# SMH118.net
KiCad netlist of a schematic drawn in Altium Designer
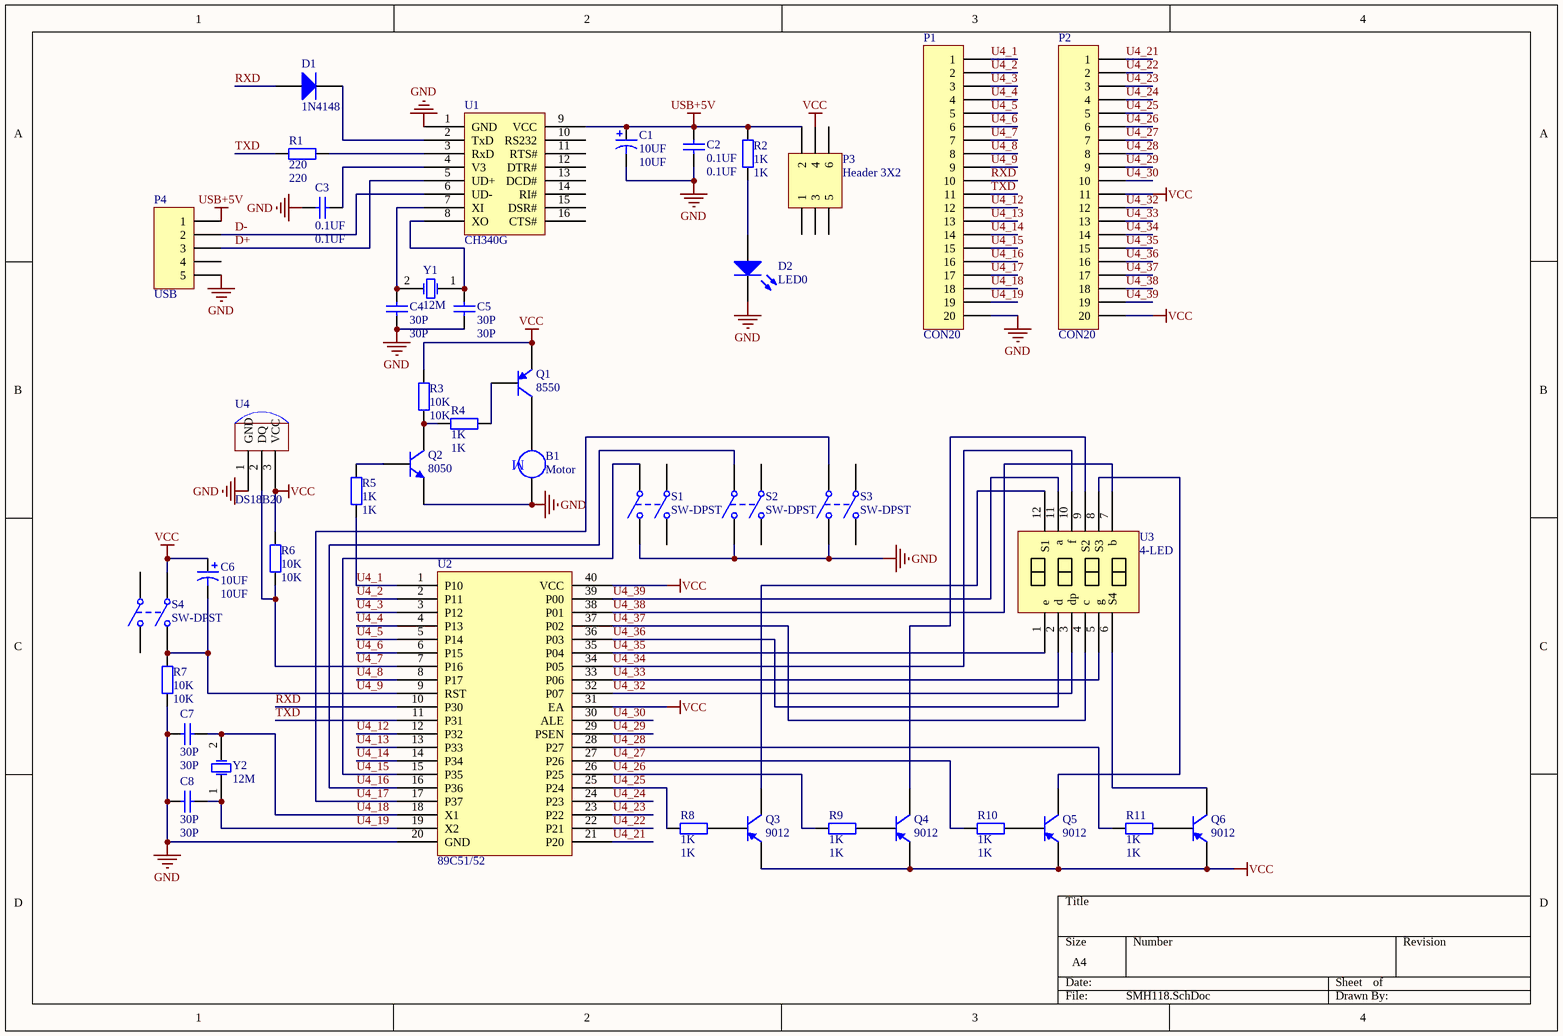
[diagram p0: SMH118.SchDoc]

(export (version "E")
  (design (tool "Eeschema 10.0.6"))
  (components
    (comp (ref "B1")
      (value "Motor")
      (footprint "XH2.54-2P")
      (description "Motor, General Kind")
      (fields (field (name "PUBLISHER") "Altium Limited"))
      (libsource (lib "Miscellaneous Devices") (part "Motor"))
    )
    (comp (ref "C1")
      (value "10UF")
      (footprint "CD4")
      (description "Polarized Capacitor (Radial)")
      (fields (field (name "ALTIUM_VALUE") "10UF") (field (name "PUBLISHER") "Altium Limited"))
      (libsource (lib "") (part "Cap Pol1_1"))
    )
    (comp (ref "C2")
      (value "0.1UF")
      (footprint "CB1")
      (description "Capacitor")
      (fields (field (name "ALTIUM_VALUE") "0.1UF") (field (name "PUBLISHER") "Altium Limited"))
      (libsource (lib "Miscellaneous Devices") (part "Cap"))
    )
    (comp (ref "C3")
      (value "0.1UF")
      (footprint "CB1")
      (description "Capacitor")
      (fields (field (name "ALTIUM_VALUE") "0.1UF") (field (name "PUBLISHER") "Altium Limited"))
      (libsource (lib "Miscellaneous Devices") (part "Cap"))
    )
    (comp (ref "C4")
      (value "30P")
      (footprint "CB1")
      (description "Capacitor")
      (fields (field (name "ALTIUM_VALUE") "30P") (field (name "PUBLISHER") "Altium Limited"))
      (libsource (lib "Miscellaneous Devices") (part "Cap"))
    )
    (comp (ref "C5")
      (value "30P")
      (footprint "CB1")
      (description "Capacitor")
      (fields (field (name "ALTIUM_VALUE") "30P") (field (name "PUBLISHER") "Altium Limited"))
      (libsource (lib "Miscellaneous Devices") (part "Cap"))
    )
    (comp (ref "C6")
      (value "10UF")
      (footprint "CD4")
      (description "Polarized Capacitor (Radial)")
      (fields (field (name "ALTIUM_VALUE") "10UF") (field (name "PUBLISHER") "Altium Limited"))
      (libsource (lib "Miscellaneous Devices") (part "Cap Pol1"))
    )
    (comp (ref "C7")
      (value "30P")
      (footprint "CB1")
      (description "Capacitor")
      (fields (field (name "ALTIUM_VALUE") "30P") (field (name "PUBLISHER") "Altium Limited"))
      (libsource (lib "Miscellaneous Devices") (part "Cap"))
    )
    (comp (ref "C8")
      (value "30P")
      (footprint "CB1")
      (description "Capacitor")
      (fields (field (name "ALTIUM_VALUE") "30P") (field (name "PUBLISHER") "Altium Limited"))
      (libsource (lib "Miscellaneous Devices") (part "Cap"))
    )
    (comp (ref "D1")
      (value "1N4148")
      (footprint "DIODE0.3")
      (description "High Conductance Fast Diode")
      (fields (field (name "PUBLISHER") "Altium Limited"))
      (libsource (lib "SMH118") (part "Diode 1N4148"))
    )
    (comp (ref "D2")
      (value "LED0")
      (footprint "LED3")
      (description "Typical INFRARED GaAs LED")
      (fields (field (name "PUBLISHER") "Altium Limited"))
      (libsource (lib "Miscellaneous Devices") (part "LED0"))
    )
    (comp (ref "P1")
      (value "CON20")
      (footprint "SIP20")
      (description "Header, 20-Pin")
      (fields (field (name "PUBLISHER") "Altium Limited"))
      (libsource (lib "Miscellaneous Connectors") (part "Header 20"))
    )
    (comp (ref "P2")
      (value "CON20")
      (footprint "SIP20")
      (description "Header, 20-Pin")
      (fields (field (name "PUBLISHER") "Altium Limited"))
      (libsource (lib "Miscellaneous Connectors") (part "Header 20"))
    )
    (comp (ref "P3")
      (value "Header 3X2")
      (footprint "SW6 - 2")
      (description "Header, 3-Pin, Dual row")
      (fields (field (name "PUBLISHER") "Altium Limited"))
      (libsource (lib "Miscellaneous Connectors") (part "Header 3X2"))
    )
    (comp (ref "P4")
      (value "USB")
      (footprint "MINIUSB")
      (description "Header, 5-Pin")
      (fields (field (name "PUBLISHER") "Altium Limited"))
      (libsource (lib "Miscellaneous Connectors") (part "Header 5"))
    )
    (comp (ref "Q1")
      (value "8550")
      (footprint "8050")
      (description "PNP Bipolar Transistor")
      (fields (field (name "PUBLISHER") "Altium Limited"))
      (libsource (lib "Miscellaneous Devices") (part "PNP"))
    )
    (comp (ref "Q2")
      (value "8050")
      (footprint "8050")
      (description "NPN Bipolar Transistor")
      (fields (field (name "PUBLISHER") "Altium Limited"))
      (libsource (lib "Miscellaneous Devices") (part "NPN"))
    )
    (comp (ref "Q3")
      (value "9012")
      (footprint "8050")
      (description "PNP Bipolar Transistor")
      (fields (field (name "PUBLISHER") "Altium Limited"))
      (libsource (lib "Miscellaneous Devices") (part "PNP"))
    )
    (comp (ref "Q4")
      (value "9012")
      (footprint "8050")
      (description "PNP Bipolar Transistor")
      (fields (field (name "PUBLISHER") "Altium Limited"))
      (libsource (lib "Miscellaneous Devices") (part "PNP"))
    )
    (comp (ref "Q5")
      (value "9012")
      (footprint "8050")
      (description "PNP Bipolar Transistor")
      (fields (field (name "PUBLISHER") "Altium Limited"))
      (libsource (lib "Miscellaneous Devices") (part "PNP"))
    )
    (comp (ref "Q6")
      (value "9012")
      (footprint "8050")
      (description "PNP Bipolar Transistor")
      (fields (field (name "PUBLISHER") "Altium Limited"))
      (libsource (lib "Miscellaneous Devices") (part "PNP"))
    )
    (comp (ref "R1")
      (value "220")
      (footprint "AXIAL-0.3")
      (description "Resistor")
      (fields (field (name "ALTIUM_VALUE") "220") (field (name "PUBLISHER") "Altium Limited"))
      (libsource (lib "Miscellaneous Devices") (part "Res2"))
    )
    (comp (ref "R2")
      (value "1K")
      (footprint "AXIAL-0.3")
      (description "Resistor")
      (fields (field (name "ALTIUM_VALUE") "1K") (field (name "PUBLISHER") "Altium Limited"))
      (libsource (lib "") (part "Res2_2"))
    )
    (comp (ref "R3")
      (value "10K")
      (footprint "AXIAL-0.3")
      (description "Resistor")
      (fields (field (name "ALTIUM_VALUE") "10K") (field (name "PUBLISHER") "Altium Limited"))
      (libsource (lib "") (part "Res2_2"))
    )
    (comp (ref "R4")
      (value "1K")
      (footprint "AXIAL-0.3")
      (description "Resistor")
      (fields (field (name "ALTIUM_VALUE") "1K") (field (name "PUBLISHER") "Altium Limited"))
      (libsource (lib "") (part "Res2_1"))
    )
    (comp (ref "R5")
      (value "1K")
      (footprint "AXIAL-0.3")
      (description "Resistor")
      (fields (field (name "ALTIUM_VALUE") "1K") (field (name "PUBLISHER") "Altium Limited"))
      (libsource (lib "") (part "Res2_3"))
    )
    (comp (ref "R6")
      (value "10K")
      (footprint "AXIAL-0.3")
      (description "Resistor")
      (fields (field (name "ALTIUM_VALUE") "10K") (field (name "PUBLISHER") "Altium Limited"))
      (libsource (lib "") (part "Res2_2"))
    )
    (comp (ref "R7")
      (value "10K")
      (footprint "AXIAL-0.3")
      (description "Resistor")
      (fields (field (name "ALTIUM_VALUE") "10K") (field (name "PUBLISHER") "Altium Limited"))
      (libsource (lib "") (part "Res2_2"))
    )
    (comp (ref "R8")
      (value "1K")
      (footprint "AXIAL-0.3")
      (description "Resistor")
      (fields (field (name "ALTIUM_VALUE") "1K") (field (name "PUBLISHER") "Altium Limited"))
      (libsource (lib "") (part "Res2_1"))
    )
    (comp (ref "R9")
      (value "1K")
      (footprint "AXIAL-0.3")
      (description "Resistor")
      (fields (field (name "ALTIUM_VALUE") "1K") (field (name "PUBLISHER") "Altium Limited"))
      (libsource (lib "") (part "Res2_1"))
    )
    (comp (ref "R10")
      (value "1K")
      (footprint "AXIAL-0.3")
      (description "Resistor")
      (fields (field (name "ALTIUM_VALUE") "1K") (field (name "PUBLISHER") "Altium Limited"))
      (libsource (lib "") (part "Res2_1"))
    )
    (comp (ref "R11")
      (value "1K")
      (footprint "AXIAL-0.3")
      (description "Resistor")
      (fields (field (name "ALTIUM_VALUE") "1K") (field (name "PUBLISHER") "Altium Limited"))
      (libsource (lib "") (part "Res2_1"))
    )
    (comp (ref "S1")
      (value "SW-DPST")
      (footprint "ANJIAN")
      (description "Double-Pole, Single-Throw Switch")
      (fields (field (name "PUBLISHER") "Altium Limited"))
      (libsource (lib "Miscellaneous Devices") (part "SW-DPST"))
    )
    (comp (ref "S2")
      (value "SW-DPST")
      (footprint "ANJIAN")
      (description "Double-Pole, Single-Throw Switch")
      (fields (field (name "PUBLISHER") "Altium Limited"))
      (libsource (lib "Miscellaneous Devices") (part "SW-DPST"))
    )
    (comp (ref "S3")
      (value "SW-DPST")
      (footprint "ANJIAN")
      (description "Double-Pole, Single-Throw Switch")
      (fields (field (name "PUBLISHER") "Altium Limited"))
      (libsource (lib "Miscellaneous Devices") (part "SW-DPST"))
    )
    (comp (ref "S4")
      (value "SW-DPST")
      (footprint "ANJIAN")
      (description "Double-Pole, Single-Throw Switch")
      (fields (field (name "PUBLISHER") "Altium Limited"))
      (libsource (lib "Miscellaneous Devices") (part "SW-DPST"))
    )
    (comp (ref "U1") (value "CH340G") (footprint "SO-16") (libsource (lib "SMH118") (part "CH340G")))
    (comp (ref "U2") (value "89C51/52") (footprint "DIP40") (libsource (lib "SMH118") (part "89C51/52")))
    (comp (ref "U3") (value "4-LED") (footprint ".3684") (libsource (lib "SMH118") (part "4-LED")))
    (comp (ref "U4") (value "DS18B20") (footprint "SIP3") (libsource (lib "SMH118") (part "DS18B20")))
    (comp (ref "Y1")
      (value "12M")
      (footprint "JZ")
      (description "Crystal Oscillator")
      (fields (field (name "PUBLISHER") "Altium Limited"))
      (libsource (lib "Miscellaneous Devices") (part "XTAL"))
    )
    (comp (ref "Y2")
      (value "12M")
      (footprint "JZ")
      (description "Crystal Oscillator")
      (fields (field (name "PUBLISHER") "Altium Limited"))
      (libsource (lib "Miscellaneous Devices") (part "XTAL"))
    )
  )
  (nets
    (net (code "1") (name "/D+") (class "Default")
      (node (ref "P4") (pin "3") (pinfunction "3_3") (pintype "passive"))
      (node (ref "U1") (pin "5") (pinfunction "UD+_5") (pintype "passive"))
    )
    (net (code "2") (name "/D-") (class "Default")
      (node (ref "P4") (pin "2") (pinfunction "2_2") (pintype "passive"))
      (node (ref "U1") (pin "6") (pinfunction "UD-_6") (pintype "passive"))
    )
    (net (code "3") (name "/RXD") (class "Default")
      (node (ref "D1") (pin "1") (pinfunction "A_1") (pintype "passive"))
      (node (ref "P1") (pin "10") (pinfunction "10_10") (pintype "passive"))
      (node (ref "U2") (pin "10") (pinfunction "P30_10") (pintype "passive"))
    )
    (net (code "4") (name "/TXD") (class "Default")
      (node (ref "P1") (pin "11") (pinfunction "11_11") (pintype "passive"))
      (node (ref "R1") (pin "1") (pinfunction "1_1") (pintype "passive"))
      (node (ref "U2") (pin "11") (pinfunction "P31_11") (pintype "passive"))
    )
    (net (code "5") (name "/U4_1") (class "Default")
      (node (ref "P1") (pin "1") (pinfunction "1_1") (pintype "passive"))
      (node (ref "R5") (pin "2") (pinfunction "2_2") (pintype "passive"))
      (node (ref "U2") (pin "1") (pinfunction "P10_1") (pintype "passive"))
    )
    (net (code "6") (name "/U4_2") (class "Default")
      (node (ref "P1") (pin "2") (pinfunction "2_2") (pintype "passive"))
      (node (ref "U2") (pin "2") (pinfunction "P11_2") (pintype "passive"))
    )
    (net (code "7") (name "/U4_3") (class "Default")
      (node (ref "P1") (pin "3") (pinfunction "3_3") (pintype "passive"))
      (node (ref "U2") (pin "3") (pinfunction "P12_3") (pintype "passive"))
    )
    (net (code "8") (name "/U4_4") (class "Default")
      (node (ref "P1") (pin "4") (pinfunction "4_4") (pintype "passive"))
      (node (ref "U2") (pin "4") (pinfunction "P13_4") (pintype "passive"))
    )
    (net (code "9") (name "/U4_5") (class "Default")
      (node (ref "P1") (pin "5") (pinfunction "5_5") (pintype "passive"))
      (node (ref "U2") (pin "5") (pinfunction "P14_5") (pintype "passive"))
    )
    (net (code "10") (name "/U4_6") (class "Default")
      (node (ref "P1") (pin "6") (pinfunction "6_6") (pintype "passive"))
      (node (ref "U2") (pin "6") (pinfunction "P15_6") (pintype "passive"))
    )
    (net (code "11") (name "/U4_7") (class "Default")
      (node (ref "P1") (pin "7") (pinfunction "7_7") (pintype "passive"))
      (node (ref "R6") (pin "1") (pinfunction "1_1") (pintype "passive"))
      (node (ref "U2") (pin "7") (pinfunction "P16_7") (pintype "passive"))
      (node (ref "U4") (pin "2") (pinfunction "DQ_2") (pintype "passive"))
    )
    (net (code "12") (name "/U4_8") (class "Default")
      (node (ref "P1") (pin "8") (pinfunction "8_8") (pintype "passive"))
      (node (ref "U2") (pin "8") (pinfunction "P17_8") (pintype "passive"))
    )
    (net (code "13") (name "/U4_9") (class "Default")
      (node (ref "C6") (pin "2") (pinfunction "2_2") (pintype "passive"))
      (node (ref "P1") (pin "9") (pinfunction "9_9") (pintype "passive"))
      (node (ref "R7") (pin "2") (pinfunction "2_2") (pintype "passive"))
      (node (ref "S4") (pin "4") (pinfunction "NO2_4") (pintype "passive"))
      (node (ref "U2") (pin "9") (pinfunction "RST_9") (pintype "passive"))
    )
    (net (code "14") (name "/U4_12") (class "Default")
      (node (ref "P1") (pin "12") (pinfunction "12_12") (pintype "passive"))
      (node (ref "U2") (pin "12") (pinfunction "P32_12") (pintype "passive"))
    )
    (net (code "15") (name "/U4_13") (class "Default")
      (node (ref "P1") (pin "13") (pinfunction "13_13") (pintype "passive"))
      (node (ref "U2") (pin "13") (pinfunction "P33_13") (pintype "passive"))
    )
    (net (code "16") (name "/U4_14") (class "Default")
      (node (ref "P1") (pin "14") (pinfunction "14_14") (pintype "passive"))
      (node (ref "U2") (pin "14") (pinfunction "P34_14") (pintype "passive"))
    )
    (net (code "17") (name "/U4_15") (class "Default")
      (node (ref "P1") (pin "15") (pinfunction "15_15") (pintype "passive"))
      (node (ref "S1") (pin "1") (pinfunction "COMMON1_1") (pintype "passive"))
      (node (ref "U2") (pin "15") (pinfunction "P35_15") (pintype "passive"))
    )
    (net (code "18") (name "/U4_16") (class "Default")
      (node (ref "P1") (pin "16") (pinfunction "16_16") (pintype "passive"))
      (node (ref "S2") (pin "1") (pinfunction "COMMON1_1") (pintype "passive"))
      (node (ref "U2") (pin "16") (pinfunction "P36_16") (pintype "passive"))
    )
    (net (code "19") (name "/U4_17") (class "Default")
      (node (ref "P1") (pin "17") (pinfunction "17_17") (pintype "passive"))
      (node (ref "S3") (pin "1") (pinfunction "COMMON1_1") (pintype "passive"))
      (node (ref "U2") (pin "17") (pinfunction "P37_17") (pintype "passive"))
    )
    (net (code "20") (name "/U4_18") (class "Default")
      (node (ref "C7") (pin "2") (pinfunction "2_2") (pintype "passive"))
      (node (ref "P1") (pin "18") (pinfunction "18_18") (pintype "passive"))
      (node (ref "U2") (pin "18") (pinfunction "X1_18") (pintype "passive"))
      (node (ref "Y2") (pin "2") (pinfunction "OSC2_2") (pintype "passive"))
    )
    (net (code "21") (name "/U4_19") (class "Default")
      (node (ref "C8") (pin "2") (pinfunction "2_2") (pintype "passive"))
      (node (ref "P1") (pin "19") (pinfunction "19_19") (pintype "passive"))
      (node (ref "U2") (pin "19") (pinfunction "X2_19") (pintype "passive"))
      (node (ref "Y2") (pin "1") (pinfunction "OSC1_1") (pintype "passive"))
    )
    (net (code "22") (name "/U4_21") (class "Default")
      (node (ref "P2") (pin "1") (pinfunction "1_1") (pintype "passive"))
      (node (ref "U2") (pin "21") (pinfunction "P20_21") (pintype "passive"))
    )
    (net (code "23") (name "/U4_22") (class "Default")
      (node (ref "P2") (pin "2") (pinfunction "2_2") (pintype "passive"))
      (node (ref "U2") (pin "22") (pinfunction "P21_22") (pintype "passive"))
    )
    (net (code "24") (name "/U4_23") (class "Default")
      (node (ref "P2") (pin "3") (pinfunction "3_3") (pintype "passive"))
      (node (ref "U2") (pin "23") (pinfunction "P22_23") (pintype "passive"))
    )
    (net (code "25") (name "/U4_24") (class "Default")
      (node (ref "P2") (pin "4") (pinfunction "4_4") (pintype "passive"))
      (node (ref "U2") (pin "24") (pinfunction "P23_24") (pintype "passive"))
    )
    (net (code "26") (name "/U4_25") (class "Default")
      (node (ref "P2") (pin "5") (pinfunction "5_5") (pintype "passive"))
      (node (ref "R8") (pin "2") (pinfunction "2_2") (pintype "passive"))
      (node (ref "U2") (pin "25") (pinfunction "P24_25") (pintype "passive"))
    )
    (net (code "27") (name "/U4_26") (class "Default")
      (node (ref "P2") (pin "6") (pinfunction "6_6") (pintype "passive"))
      (node (ref "R9") (pin "2") (pinfunction "2_2") (pintype "passive"))
      (node (ref "U2") (pin "26") (pinfunction "P25_26") (pintype "passive"))
    )
    (net (code "28") (name "/U4_27") (class "Default")
      (node (ref "P2") (pin "7") (pinfunction "7_7") (pintype "passive"))
      (node (ref "R10") (pin "2") (pinfunction "2_2") (pintype "passive"))
      (node (ref "U2") (pin "27") (pinfunction "P26_27") (pintype "passive"))
    )
    (net (code "29") (name "/U4_28") (class "Default")
      (node (ref "P2") (pin "8") (pinfunction "8_8") (pintype "passive"))
      (node (ref "R11") (pin "2") (pinfunction "2_2") (pintype "passive"))
      (node (ref "U2") (pin "28") (pinfunction "P27_28") (pintype "passive"))
    )
    (net (code "30") (name "/U4_29") (class "Default")
      (node (ref "P2") (pin "9") (pinfunction "9_9") (pintype "passive"))
      (node (ref "U2") (pin "29") (pinfunction "PSEN_29") (pintype "passive"))
    )
    (net (code "31") (name "/U4_30") (class "Default")
      (node (ref "P2") (pin "10") (pinfunction "10_10") (pintype "passive"))
      (node (ref "U2") (pin "30") (pinfunction "ALE_30") (pintype "passive"))
    )
    (net (code "32") (name "/U4_32") (class "Default")
      (node (ref "P2") (pin "12") (pinfunction "12_12") (pintype "passive"))
      (node (ref "U2") (pin "32") (pinfunction "P07_32") (pintype "passive"))
      (node (ref "U3") (pin "3") (pinfunction "dp_3") (pintype "passive"))
    )
    (net (code "33") (name "/U4_33") (class "Default")
      (node (ref "P2") (pin "13") (pinfunction "13_13") (pintype "passive"))
      (node (ref "U2") (pin "33") (pinfunction "P06_33") (pintype "passive"))
      (node (ref "U3") (pin "5") (pinfunction "g_5") (pintype "passive"))
    )
    (net (code "34") (name "/U4_34") (class "Default")
      (node (ref "P2") (pin "14") (pinfunction "14_14") (pintype "passive"))
      (node (ref "U2") (pin "34") (pinfunction "P05_34") (pintype "passive"))
      (node (ref "U3") (pin "10") (pinfunction "f_10") (pintype "passive"))
    )
    (net (code "35") (name "/U4_35") (class "Default")
      (node (ref "P2") (pin "15") (pinfunction "15_15") (pintype "passive"))
      (node (ref "U2") (pin "35") (pinfunction "P04_35") (pintype "passive"))
      (node (ref "U3") (pin "1") (pinfunction "e_1") (pintype "passive"))
    )
    (net (code "36") (name "/U4_36") (class "Default")
      (node (ref "P2") (pin "16") (pinfunction "16_16") (pintype "passive"))
      (node (ref "U2") (pin "36") (pinfunction "P03_36") (pintype "passive"))
      (node (ref "U3") (pin "2") (pinfunction "d_2") (pintype "passive"))
    )
    (net (code "37") (name "/U4_37") (class "Default")
      (node (ref "P2") (pin "17") (pinfunction "17_17") (pintype "passive"))
      (node (ref "U2") (pin "37") (pinfunction "P02_37") (pintype "passive"))
      (node (ref "U3") (pin "4") (pinfunction "c_4") (pintype "passive"))
    )
    (net (code "38") (name "/U4_38") (class "Default")
      (node (ref "P2") (pin "18") (pinfunction "18_18") (pintype "passive"))
      (node (ref "U2") (pin "38") (pinfunction "P01_38") (pintype "passive"))
      (node (ref "U3") (pin "7") (pinfunction "b_7") (pintype "passive"))
    )
    (net (code "39") (name "/U4_39") (class "Default")
      (node (ref "P2") (pin "19") (pinfunction "19_19") (pintype "passive"))
      (node (ref "U2") (pin "39") (pinfunction "P00_39") (pintype "passive"))
      (node (ref "U3") (pin "11") (pinfunction "a_11") (pintype "passive"))
    )
    (net (code "40") (name "GND") (class "Default")
      (node (ref "B1") (pin "1") (pinfunction "1_1") (pintype "passive"))
      (node (ref "C1") (pin "2") (pinfunction "2_2") (pintype "passive"))
      (node (ref "C2") (pin "1") (pinfunction "1_1") (pintype "passive"))
      (node (ref "C3") (pin "1") (pinfunction "1_1") (pintype "passive"))
      (node (ref "C4") (pin "1") (pinfunction "1_1") (pintype "passive"))
      (node (ref "C5") (pin "1") (pinfunction "1_1") (pintype "passive"))
      (node (ref "C7") (pin "1") (pinfunction "1_1") (pintype "passive"))
      (node (ref "C8") (pin "1") (pinfunction "1_1") (pintype "passive"))
      (node (ref "D2") (pin "K") (pinfunction "K_K") (pintype "passive"))
      (node (ref "P1") (pin "20") (pinfunction "20_20") (pintype "passive"))
      (node (ref "P4") (pin "5") (pinfunction "5_5") (pintype "passive"))
      (node (ref "Q2") (pin "3") (pinfunction "E_3") (pintype "passive"))
      (node (ref "R7") (pin "1") (pinfunction "1_1") (pintype "passive"))
      (node (ref "S1") (pin "2") (pinfunction "NO1_2") (pintype "passive"))
      (node (ref "S2") (pin "2") (pinfunction "NO1_2") (pintype "passive"))
      (node (ref "S3") (pin "2") (pinfunction "NO1_2") (pintype "passive"))
      (node (ref "U1") (pin "1") (pinfunction "GND_1") (pintype "passive"))
      (node (ref "U2") (pin "20") (pinfunction "GND_20") (pintype "passive"))
      (node (ref "U4") (pin "1") (pinfunction "GND_1") (pintype "passive"))
    )
    (net (code "41") (name "Net-(D1-K)") (class "Default")
      (node (ref "D1") (pin "2") (pinfunction "K_2") (pintype "passive"))
      (node (ref "U1") (pin "2") (pinfunction "TxD_2") (pintype "passive"))
    )
    (net (code "42") (name "Net-(D2-PadA)") (class "Default")
      (node (ref "D2") (pin "A") (pinfunction "A_A") (pintype "passive"))
      (node (ref "R2") (pin "1") (pinfunction "1_1") (pintype "passive"))
    )
    (net (code "43") (name "Net-(Q1-B)") (class "Default")
      (node (ref "Q1") (pin "2") (pinfunction "B_2") (pintype "passive"))
      (node (ref "R4") (pin "1") (pinfunction "1_1") (pintype "passive"))
    )
    (net (code "44") (name "Net-(Q1-C)") (class "Default")
      (node (ref "B1") (pin "2") (pinfunction "2_2") (pintype "passive"))
      (node (ref "Q1") (pin "1") (pinfunction "C_1") (pintype "passive"))
    )
    (net (code "45") (name "Net-(Q2-B)") (class "Default")
      (node (ref "Q2") (pin "2") (pinfunction "B_2") (pintype "passive"))
      (node (ref "R5") (pin "1") (pinfunction "1_1") (pintype "passive"))
    )
    (net (code "46") (name "Net-(Q2-C)") (class "Default")
      (node (ref "Q2") (pin "1") (pinfunction "C_1") (pintype "passive"))
      (node (ref "R3") (pin "1") (pinfunction "1_1") (pintype "passive"))
      (node (ref "R4") (pin "2") (pinfunction "2_2") (pintype "passive"))
    )
    (net (code "47") (name "Net-(Q3-B)") (class "Default")
      (node (ref "Q3") (pin "2") (pinfunction "B_2") (pintype "passive"))
      (node (ref "R8") (pin "1") (pinfunction "1_1") (pintype "passive"))
    )
    (net (code "48") (name "Net-(Q3-C)") (class "Default")
      (node (ref "Q3") (pin "1") (pinfunction "C_1") (pintype "passive"))
      (node (ref "U3") (pin "12") (pinfunction "S1_12") (pintype "passive"))
    )
    (net (code "49") (name "Net-(Q4-B)") (class "Default")
      (node (ref "Q4") (pin "2") (pinfunction "B_2") (pintype "passive"))
      (node (ref "R9") (pin "1") (pinfunction "1_1") (pintype "passive"))
    )
    (net (code "50") (name "Net-(Q4-C)") (class "Default")
      (node (ref "Q4") (pin "1") (pinfunction "C_1") (pintype "passive"))
      (node (ref "U3") (pin "9") (pinfunction "S2_9") (pintype "passive"))
    )
    (net (code "51") (name "Net-(Q5-B)") (class "Default")
      (node (ref "Q5") (pin "2") (pinfunction "B_2") (pintype "passive"))
      (node (ref "R10") (pin "1") (pinfunction "1_1") (pintype "passive"))
    )
    (net (code "52") (name "Net-(Q5-C)") (class "Default")
      (node (ref "Q5") (pin "1") (pinfunction "C_1") (pintype "passive"))
      (node (ref "U3") (pin "8") (pinfunction "S3_8") (pintype "passive"))
    )
    (net (code "53") (name "Net-(Q6-B)") (class "Default")
      (node (ref "Q6") (pin "2") (pinfunction "B_2") (pintype "passive"))
      (node (ref "R11") (pin "1") (pinfunction "1_1") (pintype "passive"))
    )
    (net (code "54") (name "Net-(Q6-C)") (class "Default")
      (node (ref "Q6") (pin "1") (pinfunction "C_1") (pintype "passive"))
      (node (ref "U3") (pin "6") (pinfunction "S4_6") (pintype "passive"))
    )
    (net (code "55") (name "Net-(U1-RxD)") (class "Default")
      (node (ref "R1") (pin "2") (pinfunction "2_2") (pintype "passive"))
      (node (ref "U1") (pin "3") (pinfunction "RxD_3") (pintype "passive"))
    )
    (net (code "56") (name "Net-(U1-V3)") (class "Default")
      (node (ref "C3") (pin "2") (pinfunction "2_2") (pintype "passive"))
      (node (ref "U1") (pin "4") (pinfunction "V3_4") (pintype "passive"))
    )
    (net (code "57") (name "Net-(U1-XI)") (class "Default")
      (node (ref "C4") (pin "2") (pinfunction "2_2") (pintype "passive"))
      (node (ref "U1") (pin "7") (pinfunction "XI_7") (pintype "passive"))
      (node (ref "Y1") (pin "2") (pinfunction "OSC2_2") (pintype "passive"))
    )
    (net (code "58") (name "Net-(U1-XO)") (class "Default")
      (node (ref "C5") (pin "2") (pinfunction "2_2") (pintype "passive"))
      (node (ref "U1") (pin "8") (pinfunction "XO_8") (pintype "passive"))
      (node (ref "Y1") (pin "1") (pinfunction "OSC1_1") (pintype "passive"))
    )
    (net (code "59") (name "USB+5V") (class "Default")
      (node (ref "C1") (pin "1") (pinfunction "1_1") (pintype "passive"))
      (node (ref "C2") (pin "2") (pinfunction "2_2") (pintype "passive"))
      (node (ref "P3") (pin "2") (pinfunction "2_2") (pintype "passive"))
      (node (ref "P4") (pin "1") (pinfunction "1_1") (pintype "passive"))
      (node (ref "R2") (pin "2") (pinfunction "2_2") (pintype "passive"))
      (node (ref "U1") (pin "9") (pinfunction "VCC_9") (pintype "passive"))
    )
    (net (code "60") (name "VCC") (class "Default")
      (node (ref "C6") (pin "1") (pinfunction "1_1") (pintype "passive"))
      (node (ref "P2") (pin "11") (pinfunction "11_11") (pintype "passive"))
      (node (ref "P2") (pin "20") (pinfunction "20_20") (pintype "passive"))
      (node (ref "P3") (pin "4") (pinfunction "4_4") (pintype "passive"))
      (node (ref "Q1") (pin "3") (pinfunction "E_3") (pintype "passive"))
      (node (ref "Q3") (pin "3") (pinfunction "E_3") (pintype "passive"))
      (node (ref "Q4") (pin "3") (pinfunction "E_3") (pintype "passive"))
      (node (ref "Q5") (pin "3") (pinfunction "E_3") (pintype "passive"))
      (node (ref "Q6") (pin "3") (pinfunction "E_3") (pintype "passive"))
      (node (ref "R3") (pin "2") (pinfunction "2_2") (pintype "passive"))
      (node (ref "R6") (pin "2") (pinfunction "2_2") (pintype "passive"))
      (node (ref "S4") (pin "3") (pinfunction "COMMON2_3") (pintype "passive"))
      (node (ref "U2") (pin "31") (pinfunction "EA_31") (pintype "passive"))
      (node (ref "U2") (pin "40") (pinfunction "VCC_40") (pintype "passive"))
      (node (ref "U4") (pin "3") (pinfunction "VCC_3") (pintype "passive"))
    )
    (net (code "61") (name "unconnected-(P3-Pad1)") (class "Default")
      (node (ref "P3") (pin "1") (pinfunction "1_1") (pintype "passive"))
    )
    (net (code "62") (name "unconnected-(P3-Pad3)") (class "Default")
      (node (ref "P3") (pin "3") (pinfunction "3_3") (pintype "passive"))
    )
    (net (code "63") (name "unconnected-(P3-Pad5)") (class "Default")
      (node (ref "P3") (pin "5") (pinfunction "5_5") (pintype "passive"))
    )
    (net (code "64") (name "unconnected-(P3-Pad6)") (class "Default")
      (node (ref "P3") (pin "6") (pinfunction "6_6") (pintype "passive"))
    )
    (net (code "65") (name "unconnected-(P4-Pad4)") (class "Default")
      (node (ref "P4") (pin "4") (pinfunction "4_4") (pintype "passive"))
    )
    (net (code "66") (name "unconnected-(S1-COMMON2-Pad3)") (class "Default")
      (node (ref "S1") (pin "3") (pinfunction "COMMON2_3") (pintype "passive"))
    )
    (net (code "67") (name "unconnected-(S1-NO2-Pad4)") (class "Default")
      (node (ref "S1") (pin "4") (pinfunction "NO2_4") (pintype "passive"))
    )
    (net (code "68") (name "unconnected-(S2-COMMON2-Pad3)") (class "Default")
      (node (ref "S2") (pin "3") (pinfunction "COMMON2_3") (pintype "passive"))
    )
    (net (code "69") (name "unconnected-(S2-NO2-Pad4)") (class "Default")
      (node (ref "S2") (pin "4") (pinfunction "NO2_4") (pintype "passive"))
    )
    (net (code "70") (name "unconnected-(S3-COMMON2-Pad3)") (class "Default")
      (node (ref "S3") (pin "3") (pinfunction "COMMON2_3") (pintype "passive"))
    )
    (net (code "71") (name "unconnected-(S3-NO2-Pad4)") (class "Default")
      (node (ref "S3") (pin "4") (pinfunction "NO2_4") (pintype "passive"))
    )
    (net (code "72") (name "unconnected-(S4-COMMON1-Pad1)") (class "Default")
      (node (ref "S4") (pin "1") (pinfunction "COMMON1_1") (pintype "passive"))
    )
    (net (code "73") (name "unconnected-(S4-NO1-Pad2)") (class "Default")
      (node (ref "S4") (pin "2") (pinfunction "NO1_2") (pintype "passive"))
    )
    (net (code "74") (name "unconnected-(U1-CTS#-Pad16)") (class "Default")
      (node (ref "U1") (pin "16") (pinfunction "CTS#_16") (pintype "passive"))
    )
    (net (code "75") (name "unconnected-(U1-DCD#-Pad13)") (class "Default")
      (node (ref "U1") (pin "13") (pinfunction "DCD#_13") (pintype "passive"))
    )
    (net (code "76") (name "unconnected-(U1-DSR#-Pad15)") (class "Default")
      (node (ref "U1") (pin "15") (pinfunction "DSR#_15") (pintype "passive"))
    )
    (net (code "77") (name "unconnected-(U1-DTR#-Pad12)") (class "Default")
      (node (ref "U1") (pin "12") (pinfunction "DTR#_12") (pintype "passive"))
    )
    (net (code "78") (name "unconnected-(U1-RI#-Pad14)") (class "Default")
      (node (ref "U1") (pin "14") (pinfunction "RI#_14") (pintype "passive"))
    )
    (net (code "79") (name "unconnected-(U1-RS232-Pad10)") (class "Default")
      (node (ref "U1") (pin "10") (pinfunction "RS232_10") (pintype "passive"))
    )
    (net (code "80") (name "unconnected-(U1-RTS#-Pad11)") (class "Default")
      (node (ref "U1") (pin "11") (pinfunction "RTS#_11") (pintype "passive"))
    )
  )
)
